# Test_Board.net
KiCad netlist of a schematic drawn in EAGLE
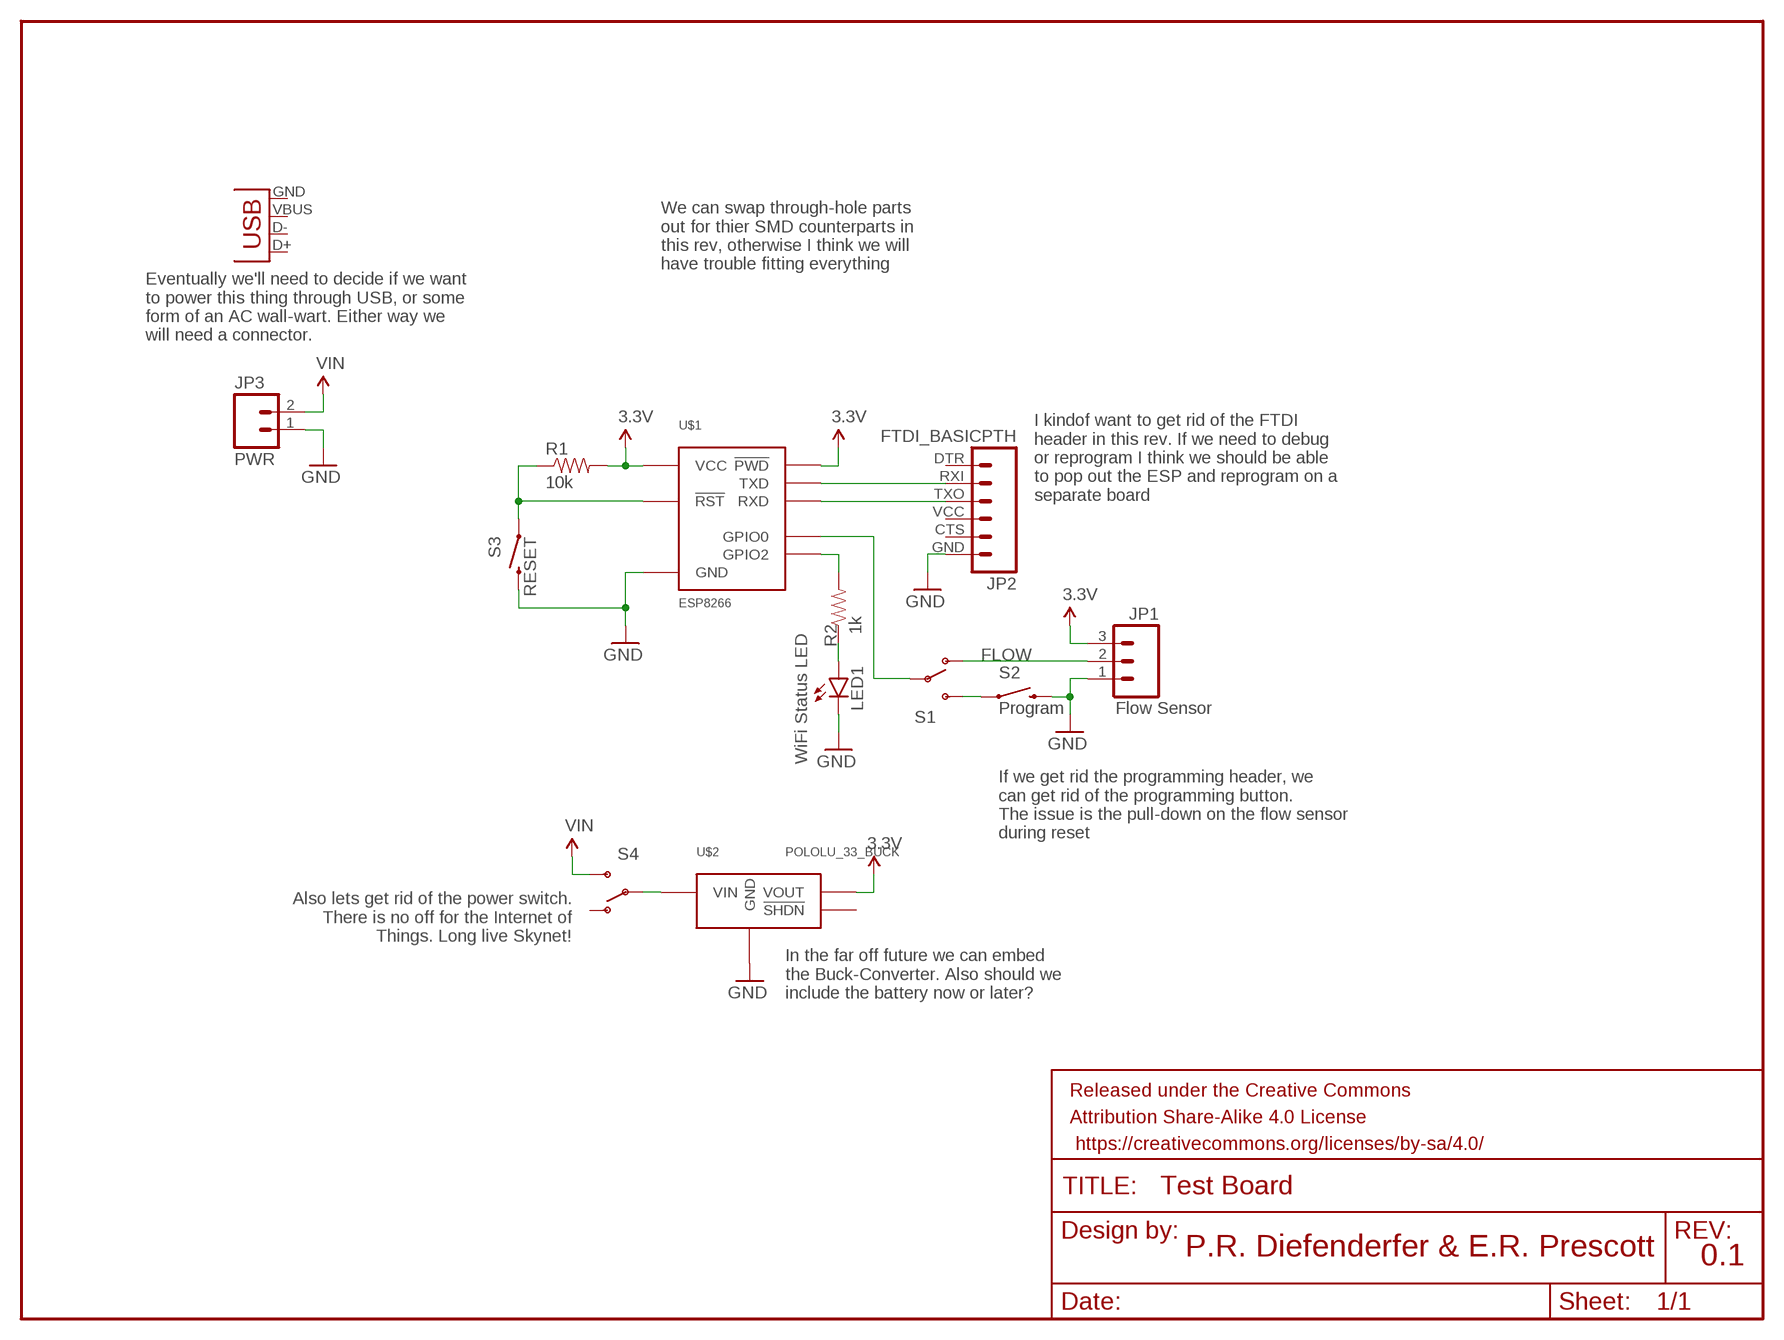
[diagram p0: schematic, sheet 1]

(export (version "E")
  (design (tool "Eeschema 10.0.6"))
  (components
    (comp (ref "FRAME1")
      (value "FRAME-LETTER")
      (footprint "eagle-import:CREATIVE_COMMONS")
      (libsource (lib "eagle-import") (part "FRAME-LETTER"))
    )
    (comp (ref "JP1")
      (value "Flow Sensor")
      (footprint "eagle-import:1X03_LOCK")
      (libsource (lib "eagle-import") (part "M03LOCK"))
    )
    (comp (ref "JP2")
      (value "FTDI_BASICPTH")
      (footprint "eagle-import:FTDI_BASIC")
      (libsource (lib "eagle-import") (part "FTDI_BASICPTH"))
    )
    (comp (ref "JP3")
      (value "PWR")
      (footprint "eagle-import:1X02_LOCK")
      (libsource (lib "eagle-import") (part "M02LOCK"))
    )
    (comp (ref "JP4")
      (value "USBSMD")
      (footprint "eagle-import:USB-MINIB")
      (libsource (lib "eagle-import") (part "USBSMD"))
    )
    (comp (ref "LED1")
      (value "WiFi Status LED")
      (footprint "eagle-import:LED3MM-NS")
      (libsource (lib "eagle-import") (part "LED-3MM-NO_SILK"))
    )
    (comp (ref "R1")
      (value "10k")
      (footprint "eagle-import:AXIAL-0.3")
      (libsource (lib "eagle-import") (part "RESISTORAXIAL-0.3"))
    )
    (comp (ref "R2")
      (value "1k")
      (footprint "eagle-import:AXIAL-0.3")
      (libsource (lib "eagle-import") (part "RESISTORAXIAL-0.3"))
    )
    (comp (ref "S1")
      (value "SWITCH-SPDTPTH")
      (footprint "eagle-import:SWITCH-SPDT")
      (libsource (lib "eagle-import") (part "SWITCH-SPDTPTH"))
    )
    (comp (ref "S2")
      (value "Program")
      (footprint "eagle-import:TACTILE-PTH")
      (libsource (lib "eagle-import") (part "SWITCH-MOMENTARY-2PTH"))
    )
    (comp (ref "S3")
      (value "RESET")
      (footprint "eagle-import:TACTILE-PTH")
      (libsource (lib "eagle-import") (part "SWITCH-MOMENTARY-2PTH"))
    )
    (comp (ref "S4")
      (value "SWITCH-SPDTPTH")
      (footprint "eagle-import:SWITCH-SPDT")
      (libsource (lib "eagle-import") (part "SWITCH-SPDTPTH"))
    )
    (comp (ref "U$1")
      (value "ESP8266")
      (footprint "eagle-import:2X4_LOCK")
      (libsource (lib "eagle-import") (part "ESP8266_R3"))
    )
    (comp (ref "U$2")
      (value "POLOLU_33_BUCK")
      (footprint "eagle-import:1X4_LOCK")
      (libsource (lib "eagle-import") (part "POLOLU_33_BUCK"))
    )
  )
  (nets
    (net (code "1") (name "/FLOW") (class "Default")
      (node (ref "JP1") (pin "2") (pinfunction "2_2") (pintype "passive"))
      (node (ref "S1") (pin "1") (pinfunction "O_1") (pintype "passive"))
    )
    (net (code "2") (name "3.3V") (class "Default")
      (node (ref "JP1") (pin "3") (pinfunction "3_3") (pintype "passive"))
      (node (ref "R1") (pin "P$2") (pinfunction "2_P$2") (pintype "passive"))
      (node (ref "U$1") (pin "CH_PD") (pinfunction "~{PWD}_CH_PD") (pintype "bidirectional"))
      (node (ref "U$1") (pin "VCC") (pinfunction "VCC_VCC") (pintype "bidirectional"))
      (node (ref "U$2") (pin "VOUT") (pinfunction "VOUT_VOUT") (pintype "bidirectional"))
    )
    (net (code "3") (name "GND") (class "Default")
      (node (ref "JP1") (pin "1") (pinfunction "1_1") (pintype "passive"))
      (node (ref "JP2") (pin "GND") (pinfunction "6_GND") (pintype "passive"))
      (node (ref "JP3") (pin "1") (pinfunction "1_1") (pintype "passive"))
      (node (ref "LED1") (pin "K") (pinfunction "C_K") (pintype "passive"))
      (node (ref "S2") (pin "3") (pinfunction "2_3") (pintype "passive"))
      (node (ref "S3") (pin "3") (pinfunction "2_3") (pintype "passive"))
      (node (ref "U$1") (pin "GND") (pinfunction "GND_GND") (pintype "bidirectional"))
      (node (ref "U$2") (pin "GND") (pinfunction "GND_GND") (pintype "bidirectional"))
    )
    (net (code "4") (name "Net-(JP2-2)") (class "Default")
      (node (ref "JP2") (pin "RXI") (pinfunction "2_RXI") (pintype "passive"))
      (node (ref "U$1") (pin "TXD") (pinfunction "TXD_TXD") (pintype "bidirectional"))
    )
    (net (code "5") (name "Net-(JP2-3)") (class "Default")
      (node (ref "JP2") (pin "TXO") (pinfunction "3_TXO") (pintype "passive"))
      (node (ref "U$1") (pin "RXD") (pinfunction "RXD_RXD") (pintype "bidirectional"))
    )
    (net (code "6") (name "Net-(R1-1)") (class "Default")
      (node (ref "R1") (pin "P$1") (pinfunction "1_P$1") (pintype "passive"))
      (node (ref "S3") (pin "1") (pinfunction "1_1") (pintype "passive"))
      (node (ref "U$1") (pin "RST") (pinfunction "~{RST}_RST") (pintype "bidirectional"))
    )
    (net (code "7") (name "Net-(R2-1)") (class "Default")
      (node (ref "LED1") (pin "A") (pinfunction "A_A") (pintype "passive"))
      (node (ref "R2") (pin "P$1") (pinfunction "1_P$1") (pintype "passive"))
    )
    (net (code "8") (name "Net-(R2-2)") (class "Default")
      (node (ref "R2") (pin "P$2") (pinfunction "2_P$2") (pintype "passive"))
      (node (ref "U$1") (pin "GPIO2") (pinfunction "GPIO2_GPIO2") (pintype "bidirectional"))
    )
    (net (code "9") (name "Net-(S1-P)") (class "Default")
      (node (ref "S1") (pin "2") (pinfunction "P_2") (pintype "passive"))
      (node (ref "U$1") (pin "GPIO0") (pinfunction "GPIO0_GPIO0") (pintype "bidirectional"))
    )
    (net (code "10") (name "Net-(S1-S)") (class "Default")
      (node (ref "S1") (pin "3") (pinfunction "S_3") (pintype "passive"))
      (node (ref "S2") (pin "1") (pinfunction "1_1") (pintype "passive"))
    )
    (net (code "11") (name "Net-(S4-P)") (class "Default")
      (node (ref "S4") (pin "2") (pinfunction "P_2") (pintype "passive"))
      (node (ref "U$2") (pin "VIN") (pinfunction "VIN_VIN") (pintype "bidirectional"))
    )
    (net (code "12") (name "VIN") (class "Default")
      (node (ref "JP3") (pin "2") (pinfunction "2_2") (pintype "passive"))
      (node (ref "S4") (pin "3") (pinfunction "S_3") (pintype "passive"))
    )
    (net (code "13") (name "unconnected-(JP2-1-PadDTR)") (class "Default")
      (node (ref "JP2") (pin "DTR") (pinfunction "1_DTR") (pintype "passive"))
    )
    (net (code "14") (name "unconnected-(JP2-4-PadVCC)") (class "Default")
      (node (ref "JP2") (pin "VCC") (pinfunction "4_VCC") (pintype "passive"))
    )
    (net (code "15") (name "unconnected-(JP2-5-PadCTS)") (class "Default")
      (node (ref "JP2") (pin "CTS") (pinfunction "5_CTS") (pintype "passive"))
    )
    (net (code "16") (name "unconnected-(JP4-PadD+)") (class "Default")
      (node (ref "JP4") (pin "D+") (pinfunction "D+_D+") (pintype "bidirectional"))
    )
    (net (code "17") (name "unconnected-(JP4-PadD-)") (class "Default")
      (node (ref "JP4") (pin "D-") (pinfunction "D-_D-") (pintype "bidirectional"))
    )
    (net (code "18") (name "unconnected-(JP4-PadGND)") (class "Default")
      (node (ref "JP4") (pin "GND") (pinfunction "GND_GND") (pintype "bidirectional"))
    )
    (net (code "19") (name "unconnected-(JP4-PadVBUS)") (class "Default")
      (node (ref "JP4") (pin "VBUS") (pinfunction "VBUS_VBUS") (pintype "bidirectional"))
    )
    (net (code "20") (name "unconnected-(S4-O-Pad1)") (class "Default")
      (node (ref "S4") (pin "1") (pinfunction "O_1") (pintype "passive"))
    )
    (net (code "21") (name "unconnected-(U$2-~{SHDN}-Pad!SHDN)") (class "Default")
      (node (ref "U$2") (pin "!SHDN") (pinfunction "~{SHDN}_!SHDN") (pintype "bidirectional"))
    )
  )
)
